# output_drivers.net
KiCad netlist of a schematic drawn in Altium Designer
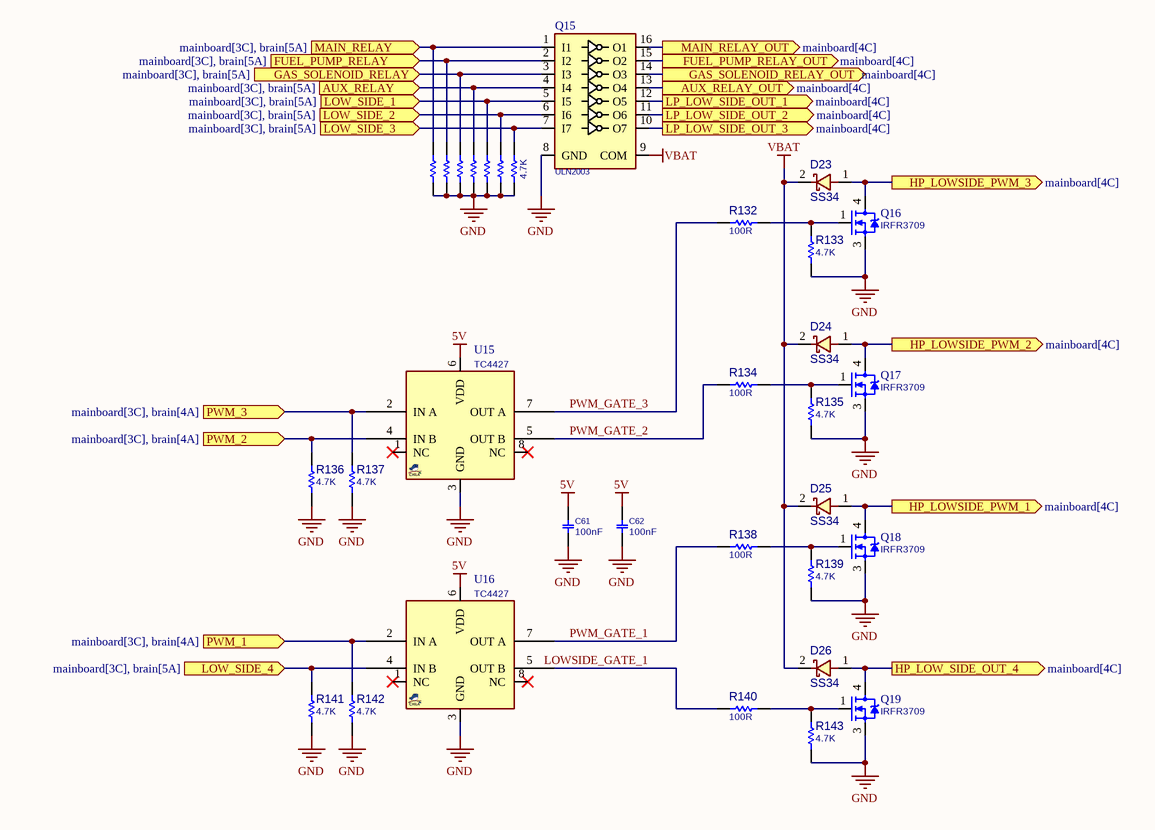
[diagram p0: output_drivers.SchDoc]

(export (version "E")
  (design (tool "Eeschema 10.0.6"))
  (components
    (comp (ref "C61")
      (value "100nF")
      (footprint "C1206")
      (description "CAP, MLCC")
      (fields (field (name "MANF_P#") "MANF_PART#") (field (name "MANF") "Murata"))
      (libsource (lib "passive_smd") (part "CAP_SMD_MLCC"))
    )
    (comp (ref "C62")
      (value "100nF")
      (footprint "C1206")
      (description "CAP, MLCC")
      (fields (field (name "MANF_P#") "MANF_PART#") (field (name "MANF") "Murata"))
      (libsource (lib "passive_smd") (part "CAP_SMD_MLCC"))
    )
    (comp (ref "D23")
      (value "SS34")
      (footprint "D_SMB")
      (description "DIODE, SCHOTTKY, 20V, 3A")
      (fields (field (name "MANF") "VISHAY"))
      (libsource (lib "diode") (part "DIODE_SMD_SCHOTTKY_SS34"))
    )
    (comp (ref "D24")
      (value "SS34")
      (footprint "D_SMB")
      (description "DIODE, SCHOTTKY, 20V, 3A")
      (fields (field (name "MANF") "VISHAY"))
      (libsource (lib "diode") (part "DIODE_SMD_SCHOTTKY_SS34"))
    )
    (comp (ref "D25")
      (value "SS34")
      (footprint "D_SMB")
      (description "DIODE, SCHOTTKY, 20V, 3A")
      (fields (field (name "MANF") "VISHAY"))
      (libsource (lib "diode") (part "DIODE_SMD_SCHOTTKY_SS34"))
    )
    (comp (ref "D26")
      (value "SS34")
      (footprint "D_SMB")
      (description "DIODE, SCHOTTKY, 20V, 3A")
      (fields (field (name "MANF") "VISHAY"))
      (libsource (lib "diode") (part "DIODE_SMD_SCHOTTKY_SS34"))
    )
    (comp (ref "Q15")
      (value "ULN2003")
      (footprint "SO_16_W")
      (description "Darlington, 7-CH, 50V, 0.5A")
      (fields (field (name "MANF_P#") "ULN2003A") (field (name "MANF") "DIODES"))
      (libsource (lib "transistor_bjt") (part "ULN2003_SOP16"))
    )
    (comp (ref "Q16")
      (value "IRFR3709")
      (footprint "DPAK_3")
      (description "MOSFET, N-CH, 30V, 86A, 6.5mRDS, 2300pF")
      (fields (field (name "MANF_P#") "IRFR3709Z"))
      (libsource (lib "transistor_fet") (part "MOSN_IRFR3709_DPAK"))
    )
    (comp (ref "Q17")
      (value "IRFR3709")
      (footprint "DPAK_3")
      (description "MOSFET, N-CH, 30V, 86A, 6.5mRDS, 2300pF")
      (fields (field (name "MANF_P#") "IRFR3709Z"))
      (libsource (lib "transistor_fet") (part "MOSN_IRFR3709_DPAK"))
    )
    (comp (ref "Q18")
      (value "IRFR3709")
      (footprint "DPAK_3")
      (description "MOSFET, N-CH, 30V, 86A, 6.5mRDS, 2300pF")
      (fields (field (name "MANF_P#") "IRFR3709Z"))
      (libsource (lib "transistor_fet") (part "MOSN_IRFR3709_DPAK"))
    )
    (comp (ref "Q19")
      (value "IRFR3709")
      (footprint "DPAK_3")
      (description "MOSFET, N-CH, 30V, 86A, 6.5mRDS, 2300pF")
      (fields (field (name "MANF_P#") "IRFR3709Z"))
      (libsource (lib "transistor_fet") (part "MOSN_IRFR3709_DPAK"))
    )
    (comp (ref "R125")
      (value "4.7K")
      (footprint "R0805")
      (description "RESISTOR, SMD")
      (libsource (lib "passive_smd") (part "RES_SMD_0805"))
    )
    (comp (ref "R126")
      (value "4.7K")
      (footprint "R0805")
      (description "RESISTOR, SMD")
      (libsource (lib "passive_smd") (part "RES_SMD_0805"))
    )
    (comp (ref "R127")
      (value "4.7K")
      (footprint "R0805")
      (description "RESISTOR, SMD")
      (libsource (lib "passive_smd") (part "RES_SMD_0805"))
    )
    (comp (ref "R128")
      (value "4.7K")
      (footprint "R0805")
      (description "RESISTOR, SMD")
      (libsource (lib "passive_smd") (part "RES_SMD_0805"))
    )
    (comp (ref "R129")
      (value "4.7K")
      (footprint "R0805")
      (description "RESISTOR, SMD")
      (libsource (lib "passive_smd") (part "RES_SMD_0805"))
    )
    (comp (ref "R130")
      (value "4.7K")
      (footprint "R0805")
      (description "RESISTOR, SMD")
      (libsource (lib "passive_smd") (part "RES_SMD_0805"))
    )
    (comp (ref "R131")
      (value "4.7K")
      (footprint "R0805")
      (description "RESISTOR, SMD")
      (libsource (lib "passive_smd") (part "RES_SMD_0805"))
    )
    (comp (ref "R132")
      (value "100R")
      (footprint "R0805")
      (description "RESISTOR, SMD")
      (libsource (lib "passive_smd") (part "RES_SMD_0805"))
    )
    (comp (ref "R133")
      (value "4.7K")
      (footprint "R0805")
      (description "RESISTOR, SMD")
      (libsource (lib "passive_smd") (part "RES_SMD_0805"))
    )
    (comp (ref "R134")
      (value "100R")
      (footprint "R0805")
      (description "RESISTOR, SMD")
      (libsource (lib "passive_smd") (part "RES_SMD_0805"))
    )
    (comp (ref "R135")
      (value "4.7K")
      (footprint "R0805")
      (description "RESISTOR, SMD")
      (libsource (lib "passive_smd") (part "RES_SMD_0805"))
    )
    (comp (ref "R136")
      (value "4.7K")
      (footprint "R0805")
      (description "RESISTOR, SMD")
      (libsource (lib "passive_smd") (part "RES_SMD_0805"))
    )
    (comp (ref "R137")
      (value "4.7K")
      (footprint "R0805")
      (description "RESISTOR, SMD")
      (libsource (lib "passive_smd") (part "RES_SMD_0805"))
    )
    (comp (ref "R138")
      (value "100R")
      (footprint "R0805")
      (description "RESISTOR, SMD")
      (libsource (lib "passive_smd") (part "RES_SMD_0805"))
    )
    (comp (ref "R139")
      (value "4.7K")
      (footprint "R0805")
      (description "RESISTOR, SMD")
      (libsource (lib "passive_smd") (part "RES_SMD_0805"))
    )
    (comp (ref "R140")
      (value "100R")
      (footprint "R0805")
      (description "RESISTOR, SMD")
      (libsource (lib "passive_smd") (part "RES_SMD_0805"))
    )
    (comp (ref "R141")
      (value "4.7K")
      (footprint "R0805")
      (description "RESISTOR, SMD")
      (libsource (lib "passive_smd") (part "RES_SMD_0805"))
    )
    (comp (ref "R142")
      (value "4.7K")
      (footprint "R0805")
      (description "RESISTOR, SMD")
      (libsource (lib "passive_smd") (part "RES_SMD_0805"))
    )
    (comp (ref "R143")
      (value "4.7K")
      (footprint "R0805")
      (description "RESISTOR, SMD")
      (libsource (lib "passive_smd") (part "RES_SMD_0805"))
    )
    (comp (ref "U15")
      (value "TC4427")
      (footprint "SO_8")
      (description "power Mosfet Driver, Dual, High-Speed, 1.5A")
      (libsource (lib "transistor_fet") (part "MOS_DUAL_TC4427"))
    )
    (comp (ref "U16")
      (value "TC4427")
      (footprint "SO_8")
      (description "power Mosfet Driver, Dual, High-Speed, 1.5A")
      (libsource (lib "transistor_fet") (part "MOS_DUAL_TC4427"))
    )
  )
  (nets
    (net (code "1") (name "/AUX_RELAY") (class "Default")
      (node (ref "Q15") (pin "4") (pinfunction "I4_4") (pintype "passive"))
      (node (ref "R128") (pin "2") (pinfunction "2_2") (pintype "passive"))
    )
    (net (code "2") (name "/AUX_RELAY_OUT") (class "Default")
      (node (ref "Q15") (pin "13") (pinfunction "O4_13") (pintype "passive"))
    )
    (net (code "3") (name "/FUEL_PUMP_RELAY") (class "Default")
      (node (ref "Q15") (pin "2") (pinfunction "I2_2") (pintype "passive"))
      (node (ref "R126") (pin "2") (pinfunction "2_2") (pintype "passive"))
    )
    (net (code "4") (name "/FUEL_PUMP_RELAY_OUT") (class "Default")
      (node (ref "Q15") (pin "15") (pinfunction "O2_15") (pintype "passive"))
    )
    (net (code "5") (name "/GAS_SOLENOID_RELAY") (class "Default")
      (node (ref "Q15") (pin "3") (pinfunction "I3_3") (pintype "passive"))
      (node (ref "R127") (pin "2") (pinfunction "2_2") (pintype "passive"))
    )
    (net (code "6") (name "/GAS_SOLENOID_RELAY_OUT") (class "Default")
      (node (ref "Q15") (pin "14") (pinfunction "O3_14") (pintype "passive"))
    )
    (net (code "7") (name "/HP_LOWSIDE_PWM_1") (class "Default")
      (node (ref "D25") (pin "1") (pinfunction "1_1") (pintype "passive"))
      (node (ref "Q18") (pin "4") (pinfunction "D_4") (pintype "passive"))
    )
    (net (code "8") (name "/HP_LOWSIDE_PWM_2") (class "Default")
      (node (ref "D24") (pin "1") (pinfunction "1_1") (pintype "passive"))
      (node (ref "Q17") (pin "4") (pinfunction "D_4") (pintype "passive"))
    )
    (net (code "9") (name "/HP_LOWSIDE_PWM_3") (class "Default")
      (node (ref "D23") (pin "1") (pinfunction "1_1") (pintype "passive"))
      (node (ref "Q16") (pin "4") (pinfunction "D_4") (pintype "passive"))
    )
    (net (code "10") (name "/HP_LOW_SIDE_OUT_4") (class "Default")
      (node (ref "D26") (pin "1") (pinfunction "1_1") (pintype "passive"))
      (node (ref "Q19") (pin "4") (pinfunction "D_4") (pintype "passive"))
    )
    (net (code "11") (name "/LOWSIDE_GATE_1") (class "Default")
      (node (ref "R140") (pin "2") (pinfunction "2_2") (pintype "passive"))
      (node (ref "U16") (pin "5") (pinfunction "OUT_B_5") (pintype "passive"))
    )
    (net (code "12") (name "/LOW_SIDE_1") (class "Default")
      (node (ref "Q15") (pin "5") (pinfunction "I5_5") (pintype "passive"))
      (node (ref "R129") (pin "2") (pinfunction "2_2") (pintype "passive"))
    )
    (net (code "13") (name "/LOW_SIDE_2") (class "Default")
      (node (ref "Q15") (pin "6") (pinfunction "I6_6") (pintype "passive"))
      (node (ref "R130") (pin "2") (pinfunction "2_2") (pintype "passive"))
    )
    (net (code "14") (name "/LOW_SIDE_3") (class "Default")
      (node (ref "Q15") (pin "7") (pinfunction "I7_7") (pintype "passive"))
      (node (ref "R131") (pin "2") (pinfunction "2_2") (pintype "passive"))
    )
    (net (code "15") (name "/LOW_SIDE_4") (class "Default")
      (node (ref "R141") (pin "2") (pinfunction "2_2") (pintype "passive"))
      (node (ref "U16") (pin "4") (pinfunction "IN_B_4") (pintype "passive"))
    )
    (net (code "16") (name "/LP_LOW_SIDE_OUT_1") (class "Default")
      (node (ref "Q15") (pin "12") (pinfunction "O5_12") (pintype "passive"))
    )
    (net (code "17") (name "/LP_LOW_SIDE_OUT_2") (class "Default")
      (node (ref "Q15") (pin "11") (pinfunction "O6_11") (pintype "passive"))
    )
    (net (code "18") (name "/LP_LOW_SIDE_OUT_3") (class "Default")
      (node (ref "Q15") (pin "10") (pinfunction "O7_10") (pintype "passive"))
    )
    (net (code "19") (name "/MAIN_RELAY") (class "Default")
      (node (ref "Q15") (pin "1") (pinfunction "I1_1") (pintype "passive"))
      (node (ref "R125") (pin "2") (pinfunction "2_2") (pintype "passive"))
    )
    (net (code "20") (name "/MAIN_RELAY_OUT") (class "Default")
      (node (ref "Q15") (pin "16") (pinfunction "O1_16") (pintype "passive"))
    )
    (net (code "21") (name "/PWM_1") (class "Default")
      (node (ref "R142") (pin "2") (pinfunction "2_2") (pintype "passive"))
      (node (ref "U16") (pin "2") (pinfunction "IN_A_2") (pintype "passive"))
    )
    (net (code "22") (name "/PWM_2") (class "Default")
      (node (ref "R136") (pin "2") (pinfunction "2_2") (pintype "passive"))
      (node (ref "U15") (pin "4") (pinfunction "IN_B_4") (pintype "passive"))
    )
    (net (code "23") (name "/PWM_3") (class "Default")
      (node (ref "R137") (pin "2") (pinfunction "2_2") (pintype "passive"))
      (node (ref "U15") (pin "2") (pinfunction "IN_A_2") (pintype "passive"))
    )
    (net (code "24") (name "/PWM_GATE_1") (class "Default")
      (node (ref "R138") (pin "2") (pinfunction "2_2") (pintype "passive"))
      (node (ref "U16") (pin "7") (pinfunction "OUT_A_7") (pintype "passive"))
    )
    (net (code "25") (name "/PWM_GATE_2") (class "Default")
      (node (ref "R134") (pin "2") (pinfunction "2_2") (pintype "passive"))
      (node (ref "U15") (pin "5") (pinfunction "OUT_B_5") (pintype "passive"))
    )
    (net (code "26") (name "/PWM_GATE_3") (class "Default")
      (node (ref "R132") (pin "2") (pinfunction "2_2") (pintype "passive"))
      (node (ref "U15") (pin "7") (pinfunction "OUT_A_7") (pintype "passive"))
    )
    (net (code "27") (name "5V") (class "Default")
      (node (ref "C61") (pin "2") (pinfunction "2_2") (pintype "passive"))
      (node (ref "C62") (pin "2") (pinfunction "2_2") (pintype "passive"))
      (node (ref "U15") (pin "6") (pinfunction "VDD_6") (pintype "passive"))
      (node (ref "U16") (pin "6") (pinfunction "VDD_6") (pintype "passive"))
    )
    (net (code "28") (name "GND") (class "Default")
      (node (ref "C61") (pin "1") (pinfunction "1_1") (pintype "passive"))
      (node (ref "C62") (pin "1") (pinfunction "1_1") (pintype "passive"))
      (node (ref "Q15") (pin "8") (pinfunction "GND_8") (pintype "passive"))
      (node (ref "Q16") (pin "3") (pinfunction "S_3") (pintype "passive"))
      (node (ref "Q17") (pin "3") (pinfunction "S_3") (pintype "passive"))
      (node (ref "Q18") (pin "3") (pinfunction "S_3") (pintype "passive"))
      (node (ref "Q19") (pin "3") (pinfunction "S_3") (pintype "passive"))
      (node (ref "R125") (pin "1") (pinfunction "1_1") (pintype "passive"))
      (node (ref "R126") (pin "1") (pinfunction "1_1") (pintype "passive"))
      (node (ref "R127") (pin "1") (pinfunction "1_1") (pintype "passive"))
      (node (ref "R128") (pin "1") (pinfunction "1_1") (pintype "passive"))
      (node (ref "R129") (pin "1") (pinfunction "1_1") (pintype "passive"))
      (node (ref "R130") (pin "1") (pinfunction "1_1") (pintype "passive"))
      (node (ref "R131") (pin "1") (pinfunction "1_1") (pintype "passive"))
      (node (ref "R133") (pin "1") (pinfunction "1_1") (pintype "passive"))
      (node (ref "R135") (pin "1") (pinfunction "1_1") (pintype "passive"))
      (node (ref "R136") (pin "1") (pinfunction "1_1") (pintype "passive"))
      (node (ref "R137") (pin "1") (pinfunction "1_1") (pintype "passive"))
      (node (ref "R139") (pin "1") (pinfunction "1_1") (pintype "passive"))
      (node (ref "R141") (pin "1") (pinfunction "1_1") (pintype "passive"))
      (node (ref "R142") (pin "1") (pinfunction "1_1") (pintype "passive"))
      (node (ref "R143") (pin "1") (pinfunction "1_1") (pintype "passive"))
      (node (ref "U15") (pin "3") (pinfunction "GND_3") (pintype "passive"))
      (node (ref "U16") (pin "3") (pinfunction "GND_3") (pintype "passive"))
    )
    (net (code "29") (name "Net-(Q16-G)") (class "Default")
      (node (ref "Q16") (pin "1") (pinfunction "G_1") (pintype "passive"))
      (node (ref "R132") (pin "1") (pinfunction "1_1") (pintype "passive"))
      (node (ref "R133") (pin "2") (pinfunction "2_2") (pintype "passive"))
    )
    (net (code "30") (name "Net-(Q17-G)") (class "Default")
      (node (ref "Q17") (pin "1") (pinfunction "G_1") (pintype "passive"))
      (node (ref "R134") (pin "1") (pinfunction "1_1") (pintype "passive"))
      (node (ref "R135") (pin "2") (pinfunction "2_2") (pintype "passive"))
    )
    (net (code "31") (name "Net-(Q18-G)") (class "Default")
      (node (ref "Q18") (pin "1") (pinfunction "G_1") (pintype "passive"))
      (node (ref "R138") (pin "1") (pinfunction "1_1") (pintype "passive"))
      (node (ref "R139") (pin "2") (pinfunction "2_2") (pintype "passive"))
    )
    (net (code "32") (name "Net-(Q19-G)") (class "Default")
      (node (ref "Q19") (pin "1") (pinfunction "G_1") (pintype "passive"))
      (node (ref "R140") (pin "1") (pinfunction "1_1") (pintype "passive"))
      (node (ref "R143") (pin "2") (pinfunction "2_2") (pintype "passive"))
    )
    (net (code "33") (name "VBAT") (class "Default")
      (node (ref "D23") (pin "2") (pinfunction "2_2") (pintype "passive"))
      (node (ref "D24") (pin "2") (pinfunction "2_2") (pintype "passive"))
      (node (ref "D25") (pin "2") (pinfunction "2_2") (pintype "passive"))
      (node (ref "D26") (pin "2") (pinfunction "2_2") (pintype "passive"))
      (node (ref "Q15") (pin "9") (pinfunction "COM_9") (pintype "passive"))
    )
    (net (code "34") (name "unconnected-(U15-NC-Pad1)") (class "Default")
      (node (ref "U15") (pin "1") (pinfunction "NC_1") (pintype "passive+no_connect"))
    )
    (net (code "35") (name "unconnected-(U15-NC-Pad8)") (class "Default")
      (node (ref "U15") (pin "8") (pinfunction "NC_8") (pintype "passive+no_connect"))
    )
    (net (code "36") (name "unconnected-(U16-NC-Pad1)") (class "Default")
      (node (ref "U16") (pin "1") (pinfunction "NC_1") (pintype "passive+no_connect"))
    )
    (net (code "37") (name "unconnected-(U16-NC-Pad8)") (class "Default")
      (node (ref "U16") (pin "8") (pinfunction "NC_8") (pintype "passive+no_connect"))
    )
  )
)
